# back_r3.net
KiCad netlist of a schematic drawn in EAGLE
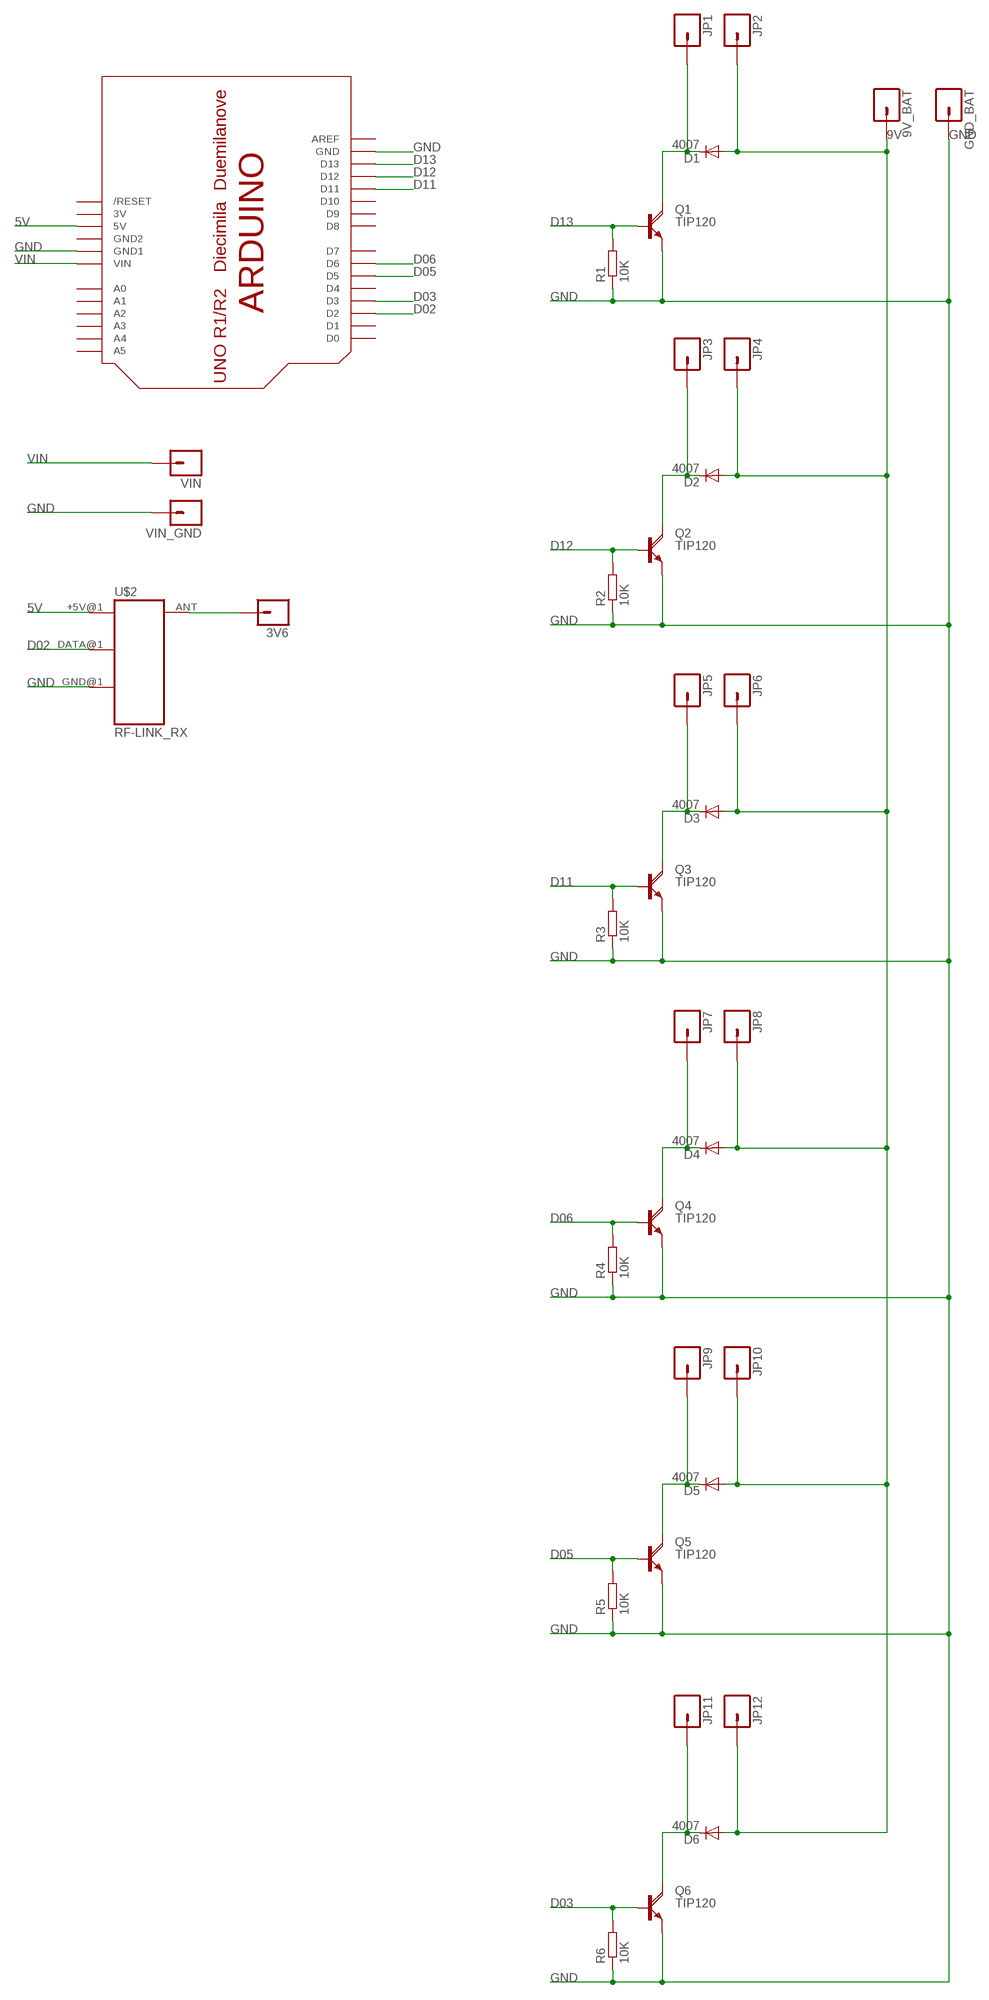
[diagram p0: schematic, sheet 1]

(export (version "E")
  (design (tool "Eeschema 10.0.6"))
  (components
    (comp (ref "3V6")
      (value "M01PTH_LONGPAD")
      (footprint "eagle-import:1X01_LONGPAD")
      (libsource (lib "eagle-import") (part "M01PTH_LONGPAD"))
    )
    (comp (ref "9V_BAT")
      (value "M01PTH_LONGPAD")
      (footprint "eagle-import:1X01_LONGPAD")
      (libsource (lib "eagle-import") (part "M01PTH_LONGPAD"))
    )
    (comp (ref "D1")
      (value "4007")
      (footprint "eagle-import:DO41-10")
      (libsource (lib "eagle-import") (part "1N4004"))
    )
    (comp (ref "D2")
      (value "4007")
      (footprint "eagle-import:DO41-10")
      (libsource (lib "eagle-import") (part "1N4004"))
    )
    (comp (ref "D3")
      (value "4007")
      (footprint "eagle-import:DO41-10")
      (libsource (lib "eagle-import") (part "1N4004"))
    )
    (comp (ref "D4")
      (value "4007")
      (footprint "eagle-import:DO41-10")
      (libsource (lib "eagle-import") (part "1N4004"))
    )
    (comp (ref "D5")
      (value "4007")
      (footprint "eagle-import:DO41-10")
      (libsource (lib "eagle-import") (part "1N4004"))
    )
    (comp (ref "D6")
      (value "4007")
      (footprint "eagle-import:DO41-10")
      (libsource (lib "eagle-import") (part "1N4004"))
    )
    (comp (ref "GND_BAT")
      (value "M01PTH_LONGPAD")
      (footprint "eagle-import:1X01_LONGPAD")
      (libsource (lib "eagle-import") (part "M01PTH_LONGPAD"))
    )
    (comp (ref "JP1")
      (value "M01PTH_LONGPAD")
      (footprint "eagle-import:1X01_LONGPAD")
      (libsource (lib "eagle-import") (part "M01PTH_LONGPAD"))
    )
    (comp (ref "JP2")
      (value "M01PTH_LONGPAD")
      (footprint "eagle-import:1X01_LONGPAD")
      (libsource (lib "eagle-import") (part "M01PTH_LONGPAD"))
    )
    (comp (ref "JP3")
      (value "M01PTH_LONGPAD")
      (footprint "eagle-import:1X01_LONGPAD")
      (libsource (lib "eagle-import") (part "M01PTH_LONGPAD"))
    )
    (comp (ref "JP4")
      (value "M01PTH_LONGPAD")
      (footprint "eagle-import:1X01_LONGPAD")
      (libsource (lib "eagle-import") (part "M01PTH_LONGPAD"))
    )
    (comp (ref "JP5")
      (value "M01PTH_LONGPAD")
      (footprint "eagle-import:1X01_LONGPAD")
      (libsource (lib "eagle-import") (part "M01PTH_LONGPAD"))
    )
    (comp (ref "JP6")
      (value "M01PTH_LONGPAD")
      (footprint "eagle-import:1X01_LONGPAD")
      (libsource (lib "eagle-import") (part "M01PTH_LONGPAD"))
    )
    (comp (ref "JP7")
      (value "M01PTH_LONGPAD")
      (footprint "eagle-import:1X01_LONGPAD")
      (libsource (lib "eagle-import") (part "M01PTH_LONGPAD"))
    )
    (comp (ref "JP8")
      (value "M01PTH_LONGPAD")
      (footprint "eagle-import:1X01_LONGPAD")
      (libsource (lib "eagle-import") (part "M01PTH_LONGPAD"))
    )
    (comp (ref "JP9")
      (value "M01PTH_LONGPAD")
      (footprint "eagle-import:1X01_LONGPAD")
      (libsource (lib "eagle-import") (part "M01PTH_LONGPAD"))
    )
    (comp (ref "JP10")
      (value "M01PTH_LONGPAD")
      (footprint "eagle-import:1X01_LONGPAD")
      (libsource (lib "eagle-import") (part "M01PTH_LONGPAD"))
    )
    (comp (ref "JP11")
      (value "M01PTH_LONGPAD")
      (footprint "eagle-import:1X01_LONGPAD")
      (libsource (lib "eagle-import") (part "M01PTH_LONGPAD"))
    )
    (comp (ref "JP12")
      (value "M01PTH_LONGPAD")
      (footprint "eagle-import:1X01_LONGPAD")
      (libsource (lib "eagle-import") (part "M01PTH_LONGPAD"))
    )
    (comp (ref "Q1")
      (value "TIP120")
      (footprint "eagle-import:TO220AH")
      (libsource (lib "eagle-import") (part "TIP120"))
    )
    (comp (ref "Q2")
      (value "TIP120")
      (footprint "eagle-import:TO220AH")
      (libsource (lib "eagle-import") (part "TIP120"))
    )
    (comp (ref "Q3")
      (value "TIP120")
      (footprint "eagle-import:TO220AH")
      (libsource (lib "eagle-import") (part "TIP120"))
    )
    (comp (ref "Q4")
      (value "TIP120")
      (footprint "eagle-import:TO220AH")
      (libsource (lib "eagle-import") (part "TIP120"))
    )
    (comp (ref "Q5")
      (value "TIP120")
      (footprint "eagle-import:TO220AH")
      (libsource (lib "eagle-import") (part "TIP120"))
    )
    (comp (ref "Q6")
      (value "TIP120")
      (footprint "eagle-import:TO220AH")
      (libsource (lib "eagle-import") (part "TIP120"))
    )
    (comp (ref "R1")
      (value "10K")
      (footprint "eagle-import:0207_10")
      (libsource (lib "eagle-import") (part "R-EU_0207/10"))
    )
    (comp (ref "R2")
      (value "10K")
      (footprint "eagle-import:0207_10")
      (libsource (lib "eagle-import") (part "R-EU_0207/10"))
    )
    (comp (ref "R3")
      (value "10K")
      (footprint "eagle-import:0207_10")
      (libsource (lib "eagle-import") (part "R-EU_0207/10"))
    )
    (comp (ref "R4")
      (value "10K")
      (footprint "eagle-import:0207_10")
      (libsource (lib "eagle-import") (part "R-EU_0207/10"))
    )
    (comp (ref "R5")
      (value "10K")
      (footprint "eagle-import:0207_10")
      (libsource (lib "eagle-import") (part "R-EU_0207/10"))
    )
    (comp (ref "R6")
      (value "10K")
      (footprint "eagle-import:0207_10")
      (libsource (lib "eagle-import") (part "R-EU_0207/10"))
    )
    (comp (ref "U$1")
      (value "ARDUINO-BPLACE")
      (footprint "eagle-import:ARDUINO-BPLACE")
      (libsource (lib "eagle-import") (part "ARDUINO-BPLACE"))
    )
    (comp (ref "U$2")
      (value "RF-LINK_RX")
      (footprint "eagle-import:RF-LINK_RX")
      (libsource (lib "eagle-import") (part "RF-LINK_RX"))
    )
    (comp (ref "VIN")
      (value "M01PTH_LONGPAD")
      (footprint "eagle-import:1X01_LONGPAD")
      (libsource (lib "eagle-import") (part "M01PTH_LONGPAD"))
    )
    (comp (ref "VIN_GND")
      (value "M01PTH_LONGPAD")
      (footprint "eagle-import:1X01_LONGPAD")
      (libsource (lib "eagle-import") (part "M01PTH_LONGPAD"))
    )
  )
  (nets
    (net (code "1") (name "/3V") (class "Default")
      (node (ref "U$1") (pin "3V") (pinfunction "3V_3V") (pintype "power_in"))
    )
    (net (code "2") (name "/5V") (class "Default")
      (node (ref "U$1") (pin "5V") (pinfunction "5V_5V") (pintype "power_in"))
      (node (ref "U$2") (pin "+5V@1") (pinfunction "+5V_+5V@1") (pintype "power_in"))
    )
    (net (code "3") (name "/9V") (class "Default")
      (node (ref "9V_BAT") (pin "1") (pinfunction "1_1") (pintype "passive"))
      (node (ref "D1") (pin "A") (pinfunction "A_A") (pintype "passive"))
      (node (ref "D2") (pin "A") (pinfunction "A_A") (pintype "passive"))
      (node (ref "D3") (pin "A") (pinfunction "A_A") (pintype "passive"))
      (node (ref "D4") (pin "A") (pinfunction "A_A") (pintype "passive"))
      (node (ref "D5") (pin "A") (pinfunction "A_A") (pintype "passive"))
      (node (ref "D6") (pin "A") (pinfunction "A_A") (pintype "passive"))
      (node (ref "JP10") (pin "1") (pinfunction "1_1") (pintype "passive"))
      (node (ref "JP12") (pin "1") (pinfunction "1_1") (pintype "passive"))
      (node (ref "JP2") (pin "1") (pinfunction "1_1") (pintype "passive"))
      (node (ref "JP4") (pin "1") (pinfunction "1_1") (pintype "passive"))
      (node (ref "JP6") (pin "1") (pinfunction "1_1") (pintype "passive"))
      (node (ref "JP8") (pin "1") (pinfunction "1_1") (pintype "passive"))
    )
    (net (code "4") (name "/D02") (class "Default")
      (node (ref "U$1") (pin "D2") (pinfunction "D2_D2") (pintype "bidirectional"))
      (node (ref "U$2") (pin "DATA@1") (pinfunction "DATA_DATA@1") (pintype "input"))
    )
    (net (code "5") (name "/D03") (class "Default")
      (node (ref "Q6") (pin "B") (pinfunction "B_B") (pintype "passive"))
      (node (ref "R6") (pin "2") (pinfunction "2_2") (pintype "passive"))
      (node (ref "U$1") (pin "D3") (pinfunction "D3_D3") (pintype "bidirectional"))
    )
    (net (code "6") (name "/D05") (class "Default")
      (node (ref "Q5") (pin "B") (pinfunction "B_B") (pintype "passive"))
      (node (ref "R5") (pin "2") (pinfunction "2_2") (pintype "passive"))
      (node (ref "U$1") (pin "D5") (pinfunction "D5_D5") (pintype "bidirectional"))
    )
    (net (code "7") (name "/D06") (class "Default")
      (node (ref "Q4") (pin "B") (pinfunction "B_B") (pintype "passive"))
      (node (ref "R4") (pin "2") (pinfunction "2_2") (pintype "passive"))
      (node (ref "U$1") (pin "D6") (pinfunction "D6_D6") (pintype "bidirectional"))
    )
    (net (code "8") (name "/D11") (class "Default")
      (node (ref "Q3") (pin "B") (pinfunction "B_B") (pintype "passive"))
      (node (ref "R3") (pin "2") (pinfunction "2_2") (pintype "passive"))
      (node (ref "U$1") (pin "D11") (pinfunction "D11_D11") (pintype "bidirectional"))
    )
    (net (code "9") (name "/D12") (class "Default")
      (node (ref "Q2") (pin "B") (pinfunction "B_B") (pintype "passive"))
      (node (ref "R2") (pin "2") (pinfunction "2_2") (pintype "passive"))
      (node (ref "U$1") (pin "D12") (pinfunction "D12_D12") (pintype "bidirectional"))
    )
    (net (code "10") (name "/D13") (class "Default")
      (node (ref "Q1") (pin "B") (pinfunction "B_B") (pintype "passive"))
      (node (ref "R1") (pin "2") (pinfunction "2_2") (pintype "passive"))
      (node (ref "U$1") (pin "D13") (pinfunction "D13_D13") (pintype "bidirectional"))
    )
    (net (code "11") (name "/GND") (class "Default")
      (node (ref "GND_BAT") (pin "1") (pinfunction "1_1") (pintype "passive"))
      (node (ref "Q1") (pin "E") (pinfunction "E_E") (pintype "passive"))
      (node (ref "Q2") (pin "E") (pinfunction "E_E") (pintype "passive"))
      (node (ref "Q3") (pin "E") (pinfunction "E_E") (pintype "passive"))
      (node (ref "Q4") (pin "E") (pinfunction "E_E") (pintype "passive"))
      (node (ref "Q5") (pin "E") (pinfunction "E_E") (pintype "passive"))
      (node (ref "Q6") (pin "E") (pinfunction "E_E") (pintype "passive"))
      (node (ref "R1") (pin "1") (pinfunction "1_1") (pintype "passive"))
      (node (ref "R2") (pin "1") (pinfunction "1_1") (pintype "passive"))
      (node (ref "R3") (pin "1") (pinfunction "1_1") (pintype "passive"))
      (node (ref "R4") (pin "1") (pinfunction "1_1") (pintype "passive"))
      (node (ref "R5") (pin "1") (pinfunction "1_1") (pintype "passive"))
      (node (ref "R6") (pin "1") (pinfunction "1_1") (pintype "passive"))
      (node (ref "U$1") (pin "GND") (pinfunction "GND_GND") (pintype "power_in"))
      (node (ref "U$1") (pin "GND1") (pinfunction "GND1_GND1") (pintype "power_in"))
      (node (ref "U$2") (pin "GND@1") (pinfunction "GND_GND@1") (pintype "power_in"))
      (node (ref "VIN_GND") (pin "1") (pinfunction "1_1") (pintype "passive"))
    )
    (net (code "12") (name "/GND2") (class "Default")
      (node (ref "U$1") (pin "GND2") (pinfunction "GND2_GND2") (pintype "power_in"))
    )
    (net (code "13") (name "/VIN") (class "Default")
      (node (ref "U$1") (pin "VIN") (pinfunction "VIN_VIN") (pintype "power_in"))
      (node (ref "VIN") (pin "1") (pinfunction "1_1") (pintype "passive"))
    )
    (net (code "14") (name "Net-(3V6-Pad1)") (class "Default")
      (node (ref "3V6") (pin "1") (pinfunction "1_1") (pintype "passive"))
      (node (ref "U$2") (pin "ANT") (pinfunction "ANT_ANT") (pintype "passive"))
    )
    (net (code "15") (name "Net-(D1-PadC)") (class "Default")
      (node (ref "D1") (pin "C") (pinfunction "C_C") (pintype "passive"))
      (node (ref "JP1") (pin "1") (pinfunction "1_1") (pintype "passive"))
      (node (ref "Q1") (pin "C") (pinfunction "C_C") (pintype "passive"))
    )
    (net (code "16") (name "Net-(D2-PadC)") (class "Default")
      (node (ref "D2") (pin "C") (pinfunction "C_C") (pintype "passive"))
      (node (ref "JP3") (pin "1") (pinfunction "1_1") (pintype "passive"))
      (node (ref "Q2") (pin "C") (pinfunction "C_C") (pintype "passive"))
    )
    (net (code "17") (name "Net-(D3-PadC)") (class "Default")
      (node (ref "D3") (pin "C") (pinfunction "C_C") (pintype "passive"))
      (node (ref "JP5") (pin "1") (pinfunction "1_1") (pintype "passive"))
      (node (ref "Q3") (pin "C") (pinfunction "C_C") (pintype "passive"))
    )
    (net (code "18") (name "Net-(D4-PadC)") (class "Default")
      (node (ref "D4") (pin "C") (pinfunction "C_C") (pintype "passive"))
      (node (ref "JP7") (pin "1") (pinfunction "1_1") (pintype "passive"))
      (node (ref "Q4") (pin "C") (pinfunction "C_C") (pintype "passive"))
    )
    (net (code "19") (name "Net-(D5-PadC)") (class "Default")
      (node (ref "D5") (pin "C") (pinfunction "C_C") (pintype "passive"))
      (node (ref "JP9") (pin "1") (pinfunction "1_1") (pintype "passive"))
      (node (ref "Q5") (pin "C") (pinfunction "C_C") (pintype "passive"))
    )
    (net (code "20") (name "Net-(D6-PadC)") (class "Default")
      (node (ref "D6") (pin "C") (pinfunction "C_C") (pintype "passive"))
      (node (ref "JP11") (pin "1") (pinfunction "1_1") (pintype "passive"))
      (node (ref "Q6") (pin "C") (pinfunction "C_C") (pintype "passive"))
    )
    (net (code "21") (name "unconnected-(U$1-PadA0)") (class "Default")
      (node (ref "U$1") (pin "A0") (pinfunction "A0_A0") (pintype "bidirectional"))
    )
    (net (code "22") (name "unconnected-(U$1-PadA1)") (class "Default")
      (node (ref "U$1") (pin "A1") (pinfunction "A1_A1") (pintype "bidirectional"))
    )
    (net (code "23") (name "unconnected-(U$1-PadA2)") (class "Default")
      (node (ref "U$1") (pin "A2") (pinfunction "A2_A2") (pintype "bidirectional"))
    )
    (net (code "24") (name "unconnected-(U$1-PadA3)") (class "Default")
      (node (ref "U$1") (pin "A3") (pinfunction "A3_A3") (pintype "bidirectional"))
    )
    (net (code "25") (name "unconnected-(U$1-PadA4)") (class "Default")
      (node (ref "U$1") (pin "A4") (pinfunction "A4_A4") (pintype "bidirectional"))
    )
    (net (code "26") (name "unconnected-(U$1-PadA5)") (class "Default")
      (node (ref "U$1") (pin "A5") (pinfunction "A5_A5") (pintype "bidirectional"))
    )
    (net (code "27") (name "unconnected-(U$1-PadAREF)") (class "Default")
      (node (ref "U$1") (pin "AREF") (pinfunction "AREF_AREF") (pintype "bidirectional"))
    )
    (net (code "28") (name "unconnected-(U$1-PadD0)") (class "Default")
      (node (ref "U$1") (pin "D0") (pinfunction "D0_D0") (pintype "bidirectional"))
    )
    (net (code "29") (name "unconnected-(U$1-PadD1)") (class "Default")
      (node (ref "U$1") (pin "D1") (pinfunction "D1_D1") (pintype "bidirectional"))
    )
    (net (code "30") (name "unconnected-(U$1-PadD4)") (class "Default")
      (node (ref "U$1") (pin "D4") (pinfunction "D4_D4") (pintype "bidirectional"))
    )
    (net (code "31") (name "unconnected-(U$1-PadD7)") (class "Default")
      (node (ref "U$1") (pin "D7") (pinfunction "D7_D7") (pintype "bidirectional"))
    )
    (net (code "32") (name "unconnected-(U$1-PadD8)") (class "Default")
      (node (ref "U$1") (pin "D8") (pinfunction "D8_D8") (pintype "bidirectional"))
    )
    (net (code "33") (name "unconnected-(U$1-PadD9)") (class "Default")
      (node (ref "U$1") (pin "D9") (pinfunction "D9_D9") (pintype "bidirectional"))
    )
    (net (code "34") (name "unconnected-(U$1-PadD10)") (class "Default")
      (node (ref "U$1") (pin "D10") (pinfunction "D10_D10") (pintype "bidirectional"))
    )
    (net (code "35") (name "unconnected-(U$1-{slash}RESET-PadRESET)") (class "Default")
      (node (ref "U$1") (pin "RESET") (pinfunction "/RESET_RESET") (pintype "bidirectional"))
    )
  )
)
